# 10_Connectors.net
KiCad netlist of a schematic drawn in Altium Designer
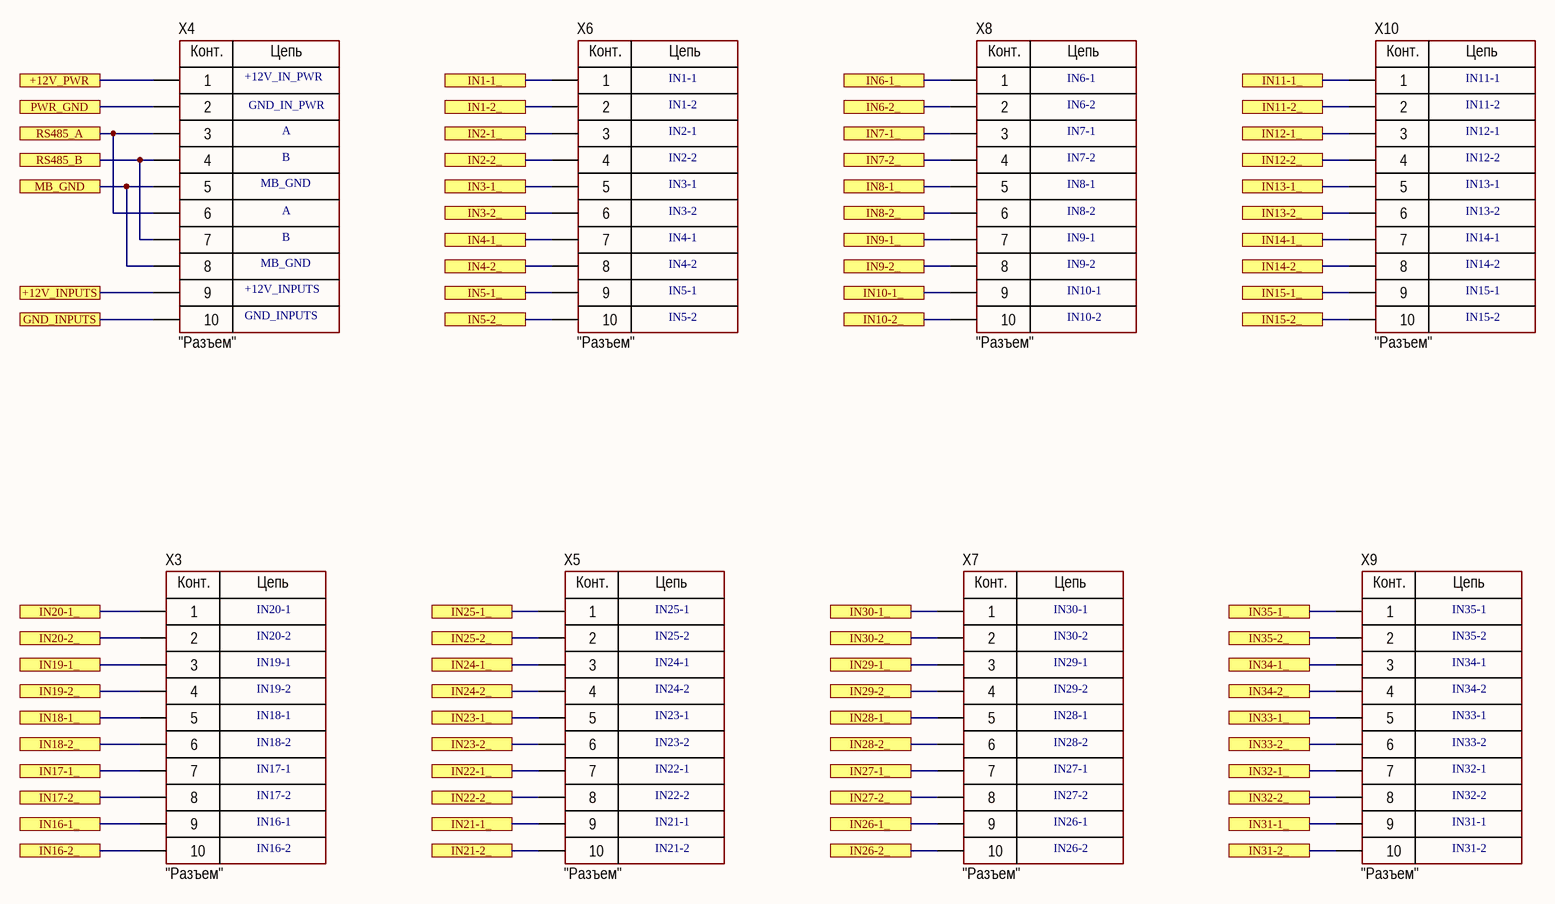
[diagram p0: 10_Connectors.SchDoc]

(export (version "E")
  (design (tool "Eeschema 10.0.6"))
  (components
    (comp (ref "X3")
      (value "~")
      (footprint "board:CON: 15EDGVC-3.5-10P-14-00AH")
      (fields
        (field (name "MANUFACTURER") "Degson")
        (field (name "VALUEMANUFACTURERPARTNUMBER") "Terminal connector, 6pin, 3.5mm, 300VAC, 10A")
        (field (name "PARTNUMBER") "15EDGVC-3.5-10P-14-00A(H)")
        (field (name "COMMENTTEXT") "\"Разъем\"")
      )
      (libsource (lib "board") (part "15EDGVC-3.5-10P-14-00A(H)"))
    )
    (comp (ref "X4")
      (value "~")
      (footprint "board:CON: 15EDGVC-3.5-10P-14-00AH")
      (fields
        (field (name "MANUFACTURER") "Degson")
        (field (name "VALUEMANUFACTURERPARTNUMBER") "Terminal connector, 6pin, 3.5mm, 300VAC, 10A")
        (field (name "PARTNUMBER") "15EDGVC-3.5-10P-14-00A(H)")
        (field (name "COMMENTTEXT") "\"Разъем\"")
      )
      (libsource (lib "board") (part "15EDGVC-3.5-10P-14-00A(H)"))
    )
    (comp (ref "X5")
      (value "~")
      (footprint "board:CON: 15EDGVC-3.5-10P-14-00AH")
      (fields
        (field (name "MANUFACTURER") "Degson")
        (field (name "VALUEMANUFACTURERPARTNUMBER") "Terminal connector, 6pin, 3.5mm, 300VAC, 10A")
        (field (name "PARTNUMBER") "15EDGVC-3.5-10P-14-00A(H)")
        (field (name "COMMENTTEXT") "\"Разъем\"")
      )
      (libsource (lib "board") (part "15EDGVC-3.5-10P-14-00A(H)"))
    )
    (comp (ref "X6")
      (value "~")
      (footprint "board:CON: 15EDGVC-3.5-10P-14-00AH")
      (fields
        (field (name "MANUFACTURER") "Degson")
        (field (name "VALUEMANUFACTURERPARTNUMBER") "Terminal connector, 6pin, 3.5mm, 300VAC, 10A")
        (field (name "PARTNUMBER") "15EDGVC-3.5-10P-14-00A(H)")
        (field (name "COMMENTTEXT") "\"Разъем\"")
      )
      (libsource (lib "board") (part "15EDGVC-3.5-10P-14-00A(H)"))
    )
    (comp (ref "X7")
      (value "~")
      (footprint "board:CON: 15EDGVC-3.5-10P-14-00AH")
      (fields
        (field (name "MANUFACTURER") "Degson")
        (field (name "VALUEMANUFACTURERPARTNUMBER") "Terminal connector, 6pin, 3.5mm, 300VAC, 10A")
        (field (name "PARTNUMBER") "15EDGVC-3.5-10P-14-00A(H)")
        (field (name "COMMENTTEXT") "\"Разъем\"")
      )
      (libsource (lib "board") (part "15EDGVC-3.5-10P-14-00A(H)"))
    )
    (comp (ref "X8")
      (value "~")
      (footprint "board:CON: 15EDGVC-3.5-10P-14-00AH")
      (fields
        (field (name "MANUFACTURER") "Degson")
        (field (name "VALUEMANUFACTURERPARTNUMBER") "Terminal connector, 6pin, 3.5mm, 300VAC, 10A")
        (field (name "PARTNUMBER") "15EDGVC-3.5-10P-14-00A(H)")
        (field (name "COMMENTTEXT") "\"Разъем\"")
      )
      (libsource (lib "board") (part "15EDGVC-3.5-10P-14-00A(H)"))
    )
    (comp (ref "X9")
      (value "~")
      (footprint "board:CON: 15EDGVC-3.5-10P-14-00AH")
      (fields
        (field (name "MANUFACTURER") "Degson")
        (field (name "VALUEMANUFACTURERPARTNUMBER") "Terminal connector, 6pin, 3.5mm, 300VAC, 10A")
        (field (name "PARTNUMBER") "15EDGVC-3.5-10P-14-00A(H)")
        (field (name "COMMENTTEXT") "\"Разъем\"")
      )
      (libsource (lib "board") (part "15EDGVC-3.5-10P-14-00A(H)"))
    )
    (comp (ref "X10")
      (value "~")
      (footprint "board:CON: 15EDGVC-3.5-10P-14-00AH")
      (fields
        (field (name "MANUFACTURER") "Degson")
        (field (name "VALUEMANUFACTURERPARTNUMBER") "Terminal connector, 6pin, 3.5mm, 300VAC, 10A")
        (field (name "PARTNUMBER") "15EDGVC-3.5-10P-14-00A(H)")
        (field (name "COMMENTTEXT") "\"Разъем\"")
      )
      (libsource (lib "board") (part "15EDGVC-3.5-10P-14-00A(H)"))
    )
  )
  (nets
    (net (code "1") (name "/+12V_INPUTS") (class "Default")
      (node (ref "X4") (pin "9") (pinfunction "9_9") (pintype "power_in"))
    )
    (net (code "2") (name "/+12V_PWR") (class "Default")
      (node (ref "X4") (pin "1") (pinfunction "1_1") (pintype "passive"))
    )
    (net (code "3") (name "/GND_INPUTS") (class "Default")
      (node (ref "X4") (pin "10") (pinfunction "10_10") (pintype "power_in"))
    )
    (net (code "4") (name "/IN1-1_") (class "Default")
      (node (ref "X6") (pin "1") (pinfunction "1_1") (pintype "passive"))
    )
    (net (code "5") (name "/IN1-2_") (class "Default")
      (node (ref "X6") (pin "2") (pinfunction "2_2") (pintype "passive"))
    )
    (net (code "6") (name "/IN2-1_") (class "Default")
      (node (ref "X6") (pin "3") (pinfunction "3_3") (pintype "power_in"))
    )
    (net (code "7") (name "/IN2-2_") (class "Default")
      (node (ref "X6") (pin "4") (pinfunction "4_4") (pintype "power_in"))
    )
    (net (code "8") (name "/IN3-1_") (class "Default")
      (node (ref "X6") (pin "5") (pinfunction "5_5") (pintype "power_in"))
    )
    (net (code "9") (name "/IN3-2_") (class "Default")
      (node (ref "X6") (pin "6") (pinfunction "6_6") (pintype "power_in"))
    )
    (net (code "10") (name "/IN4-1_") (class "Default")
      (node (ref "X6") (pin "7") (pinfunction "7_7") (pintype "power_in"))
    )
    (net (code "11") (name "/IN4-2_") (class "Default")
      (node (ref "X6") (pin "8") (pinfunction "8_8") (pintype "power_in"))
    )
    (net (code "12") (name "/IN5-1_") (class "Default")
      (node (ref "X6") (pin "9") (pinfunction "9_9") (pintype "power_in"))
    )
    (net (code "13") (name "/IN5-2_") (class "Default")
      (node (ref "X6") (pin "10") (pinfunction "10_10") (pintype "power_in"))
    )
    (net (code "14") (name "/IN6-1_") (class "Default")
      (node (ref "X8") (pin "1") (pinfunction "1_1") (pintype "passive"))
    )
    (net (code "15") (name "/IN6-2_") (class "Default")
      (node (ref "X8") (pin "2") (pinfunction "2_2") (pintype "passive"))
    )
    (net (code "16") (name "/IN7-1_") (class "Default")
      (node (ref "X8") (pin "3") (pinfunction "3_3") (pintype "power_in"))
    )
    (net (code "17") (name "/IN7-2_") (class "Default")
      (node (ref "X8") (pin "4") (pinfunction "4_4") (pintype "power_in"))
    )
    (net (code "18") (name "/IN8-1_") (class "Default")
      (node (ref "X8") (pin "5") (pinfunction "5_5") (pintype "power_in"))
    )
    (net (code "19") (name "/IN8-2_") (class "Default")
      (node (ref "X8") (pin "6") (pinfunction "6_6") (pintype "power_in"))
    )
    (net (code "20") (name "/IN9-1_") (class "Default")
      (node (ref "X8") (pin "7") (pinfunction "7_7") (pintype "power_in"))
    )
    (net (code "21") (name "/IN9-2_") (class "Default")
      (node (ref "X8") (pin "8") (pinfunction "8_8") (pintype "power_in"))
    )
    (net (code "22") (name "/IN10-1_") (class "Default")
      (node (ref "X8") (pin "9") (pinfunction "9_9") (pintype "power_in"))
    )
    (net (code "23") (name "/IN10-2_") (class "Default")
      (node (ref "X8") (pin "10") (pinfunction "10_10") (pintype "power_in"))
    )
    (net (code "24") (name "/IN11-1_") (class "Default")
      (node (ref "X10") (pin "1") (pinfunction "1_1") (pintype "passive"))
    )
    (net (code "25") (name "/IN11-2_") (class "Default")
      (node (ref "X10") (pin "2") (pinfunction "2_2") (pintype "passive"))
    )
    (net (code "26") (name "/IN12-1_") (class "Default")
      (node (ref "X10") (pin "3") (pinfunction "3_3") (pintype "power_in"))
    )
    (net (code "27") (name "/IN12-2_") (class "Default")
      (node (ref "X10") (pin "4") (pinfunction "4_4") (pintype "power_in"))
    )
    (net (code "28") (name "/IN13-1_") (class "Default")
      (node (ref "X10") (pin "5") (pinfunction "5_5") (pintype "power_in"))
    )
    (net (code "29") (name "/IN13-2_") (class "Default")
      (node (ref "X10") (pin "6") (pinfunction "6_6") (pintype "power_in"))
    )
    (net (code "30") (name "/IN14-1_") (class "Default")
      (node (ref "X10") (pin "7") (pinfunction "7_7") (pintype "power_in"))
    )
    (net (code "31") (name "/IN14-2_") (class "Default")
      (node (ref "X10") (pin "8") (pinfunction "8_8") (pintype "power_in"))
    )
    (net (code "32") (name "/IN15-1_") (class "Default")
      (node (ref "X10") (pin "9") (pinfunction "9_9") (pintype "power_in"))
    )
    (net (code "33") (name "/IN15-2_") (class "Default")
      (node (ref "X10") (pin "10") (pinfunction "10_10") (pintype "power_in"))
    )
    (net (code "34") (name "/IN16-1_") (class "Default")
      (node (ref "X3") (pin "9") (pinfunction "9_9") (pintype "power_in"))
    )
    (net (code "35") (name "/IN16-2_") (class "Default")
      (node (ref "X3") (pin "10") (pinfunction "10_10") (pintype "power_in"))
    )
    (net (code "36") (name "/IN17-1_") (class "Default")
      (node (ref "X3") (pin "7") (pinfunction "7_7") (pintype "power_in"))
    )
    (net (code "37") (name "/IN17-2_") (class "Default")
      (node (ref "X3") (pin "8") (pinfunction "8_8") (pintype "power_in"))
    )
    (net (code "38") (name "/IN18-1_") (class "Default")
      (node (ref "X3") (pin "5") (pinfunction "5_5") (pintype "power_in"))
    )
    (net (code "39") (name "/IN18-2_") (class "Default")
      (node (ref "X3") (pin "6") (pinfunction "6_6") (pintype "power_in"))
    )
    (net (code "40") (name "/IN19-1_") (class "Default")
      (node (ref "X3") (pin "3") (pinfunction "3_3") (pintype "power_in"))
    )
    (net (code "41") (name "/IN19-2_") (class "Default")
      (node (ref "X3") (pin "4") (pinfunction "4_4") (pintype "power_in"))
    )
    (net (code "42") (name "/IN20-1_") (class "Default")
      (node (ref "X3") (pin "1") (pinfunction "1_1") (pintype "passive"))
    )
    (net (code "43") (name "/IN20-2_") (class "Default")
      (node (ref "X3") (pin "2") (pinfunction "2_2") (pintype "passive"))
    )
    (net (code "44") (name "/IN21-1_") (class "Default")
      (node (ref "X5") (pin "9") (pinfunction "9_9") (pintype "power_in"))
    )
    (net (code "45") (name "/IN21-2_") (class "Default")
      (node (ref "X5") (pin "10") (pinfunction "10_10") (pintype "power_in"))
    )
    (net (code "46") (name "/IN22-1_") (class "Default")
      (node (ref "X5") (pin "7") (pinfunction "7_7") (pintype "power_in"))
    )
    (net (code "47") (name "/IN22-2_") (class "Default")
      (node (ref "X5") (pin "8") (pinfunction "8_8") (pintype "power_in"))
    )
    (net (code "48") (name "/IN23-1_") (class "Default")
      (node (ref "X5") (pin "5") (pinfunction "5_5") (pintype "power_in"))
    )
    (net (code "49") (name "/IN23-2_") (class "Default")
      (node (ref "X5") (pin "6") (pinfunction "6_6") (pintype "power_in"))
    )
    (net (code "50") (name "/IN24-1_") (class "Default")
      (node (ref "X5") (pin "3") (pinfunction "3_3") (pintype "power_in"))
    )
    (net (code "51") (name "/IN24-2_") (class "Default")
      (node (ref "X5") (pin "4") (pinfunction "4_4") (pintype "power_in"))
    )
    (net (code "52") (name "/IN25-1_") (class "Default")
      (node (ref "X5") (pin "1") (pinfunction "1_1") (pintype "passive"))
    )
    (net (code "53") (name "/IN25-2_") (class "Default")
      (node (ref "X5") (pin "2") (pinfunction "2_2") (pintype "passive"))
    )
    (net (code "54") (name "/IN26-1_") (class "Default")
      (node (ref "X7") (pin "9") (pinfunction "9_9") (pintype "power_in"))
    )
    (net (code "55") (name "/IN26-2_") (class "Default")
      (node (ref "X7") (pin "10") (pinfunction "10_10") (pintype "power_in"))
    )
    (net (code "56") (name "/IN27-1_") (class "Default")
      (node (ref "X7") (pin "7") (pinfunction "7_7") (pintype "power_in"))
    )
    (net (code "57") (name "/IN27-2_") (class "Default")
      (node (ref "X7") (pin "8") (pinfunction "8_8") (pintype "power_in"))
    )
    (net (code "58") (name "/IN28-1_") (class "Default")
      (node (ref "X7") (pin "5") (pinfunction "5_5") (pintype "power_in"))
    )
    (net (code "59") (name "/IN28-2_") (class "Default")
      (node (ref "X7") (pin "6") (pinfunction "6_6") (pintype "power_in"))
    )
    (net (code "60") (name "/IN29-1_") (class "Default")
      (node (ref "X7") (pin "3") (pinfunction "3_3") (pintype "power_in"))
    )
    (net (code "61") (name "/IN29-2_") (class "Default")
      (node (ref "X7") (pin "4") (pinfunction "4_4") (pintype "power_in"))
    )
    (net (code "62") (name "/IN30-1_") (class "Default")
      (node (ref "X7") (pin "1") (pinfunction "1_1") (pintype "passive"))
    )
    (net (code "63") (name "/IN30-2_") (class "Default")
      (node (ref "X7") (pin "2") (pinfunction "2_2") (pintype "passive"))
    )
    (net (code "64") (name "/IN31-1_") (class "Default")
      (node (ref "X9") (pin "9") (pinfunction "9_9") (pintype "power_in"))
    )
    (net (code "65") (name "/IN31-2_") (class "Default")
      (node (ref "X9") (pin "10") (pinfunction "10_10") (pintype "power_in"))
    )
    (net (code "66") (name "/IN32-1_") (class "Default")
      (node (ref "X9") (pin "7") (pinfunction "7_7") (pintype "power_in"))
    )
    (net (code "67") (name "/IN32-2_") (class "Default")
      (node (ref "X9") (pin "8") (pinfunction "8_8") (pintype "power_in"))
    )
    (net (code "68") (name "/IN33-1_") (class "Default")
      (node (ref "X9") (pin "5") (pinfunction "5_5") (pintype "power_in"))
    )
    (net (code "69") (name "/IN33-2_") (class "Default")
      (node (ref "X9") (pin "6") (pinfunction "6_6") (pintype "power_in"))
    )
    (net (code "70") (name "/IN34-1_") (class "Default")
      (node (ref "X9") (pin "3") (pinfunction "3_3") (pintype "power_in"))
    )
    (net (code "71") (name "/IN34-2_") (class "Default")
      (node (ref "X9") (pin "4") (pinfunction "4_4") (pintype "power_in"))
    )
    (net (code "72") (name "/IN35-1_") (class "Default")
      (node (ref "X9") (pin "1") (pinfunction "1_1") (pintype "passive"))
    )
    (net (code "73") (name "/IN35-2_") (class "Default")
      (node (ref "X9") (pin "2") (pinfunction "2_2") (pintype "passive"))
    )
    (net (code "74") (name "/MB_GND") (class "Default")
      (node (ref "X4") (pin "5") (pinfunction "5_5") (pintype "power_in"))
      (node (ref "X4") (pin "8") (pinfunction "8_8") (pintype "power_in"))
    )
    (net (code "75") (name "/PWR_GND") (class "Default")
      (node (ref "X4") (pin "2") (pinfunction "2_2") (pintype "passive"))
    )
    (net (code "76") (name "/RS485_A") (class "Default")
      (node (ref "X4") (pin "3") (pinfunction "3_3") (pintype "power_in"))
      (node (ref "X4") (pin "6") (pinfunction "6_6") (pintype "power_in"))
    )
    (net (code "77") (name "/RS485_B") (class "Default")
      (node (ref "X4") (pin "4") (pinfunction "4_4") (pintype "power_in"))
      (node (ref "X4") (pin "7") (pinfunction "7_7") (pintype "power_in"))
    )
  )
)
